# Sensor_Glove_Main-X01.net
KiCad netlist of a schematic drawn in Altium Designer
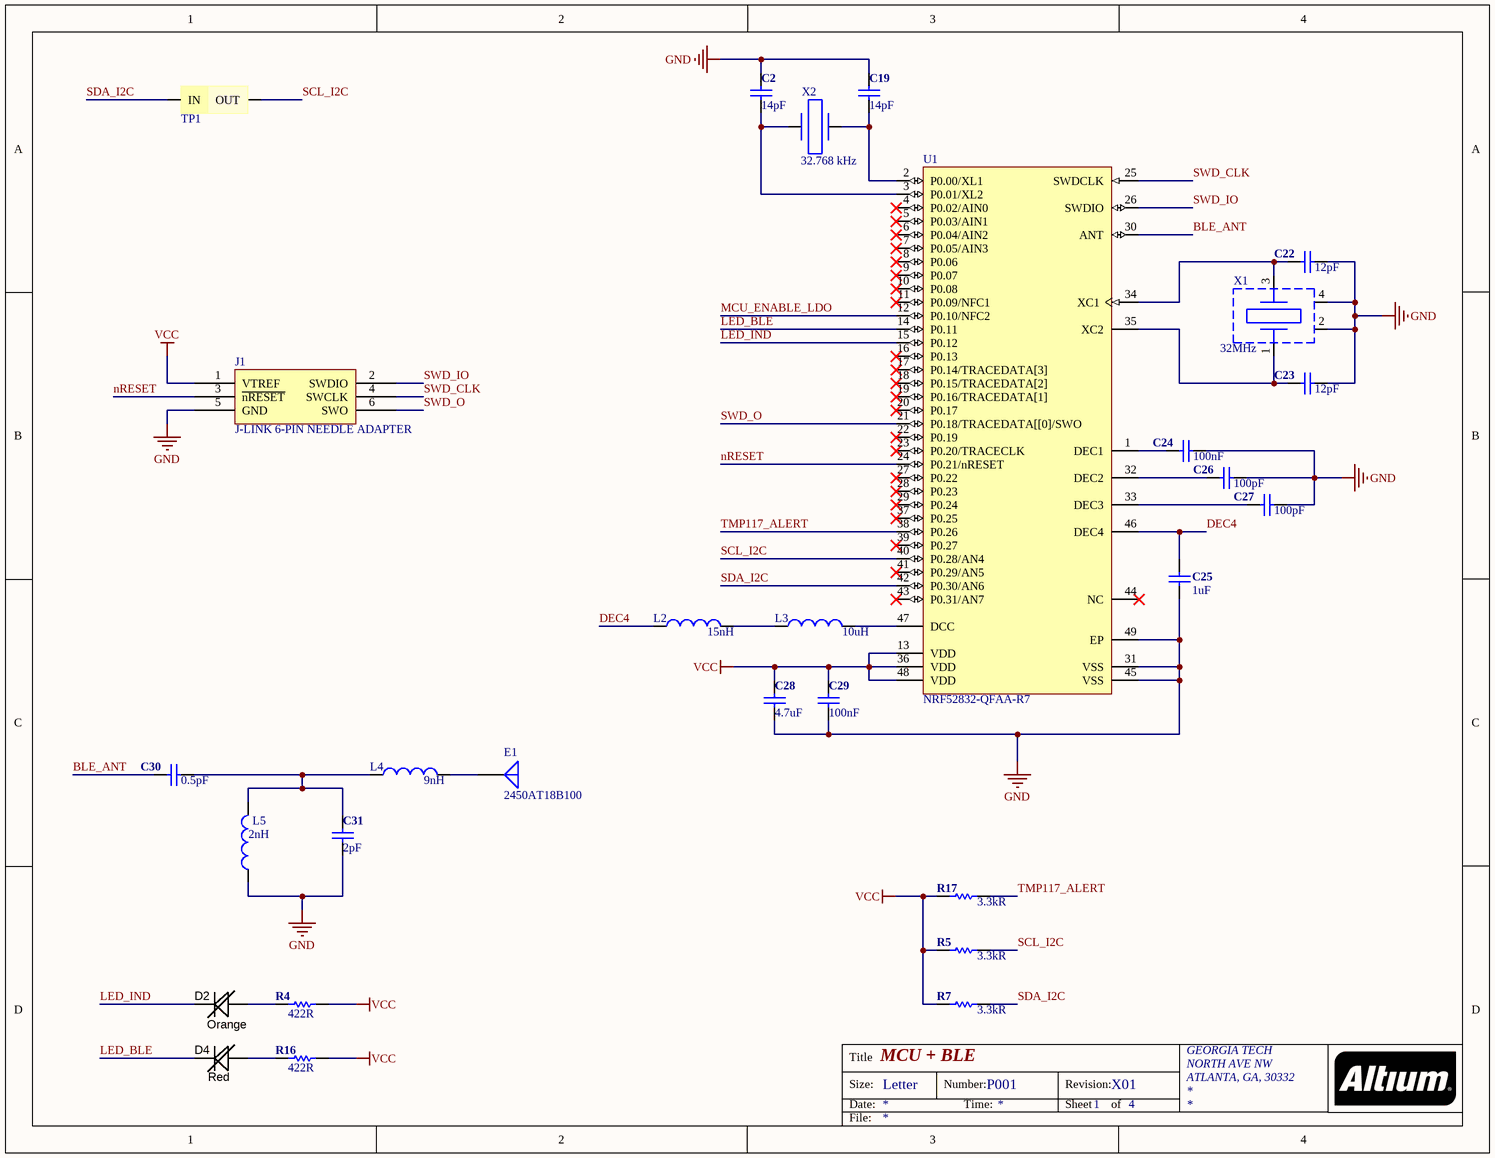
[diagram p0: Sensor_Glove_Main-X01.SchDoc]

(export (version "E")
  (design (tool "Eeschema 10.0.6"))
  (components
    (comp (ref "C2")
      (value "14pF")
      (footprint "C0402")
      (fields
        (field (name "MANUFACTURER") "Kyocera AVX")
        (field (name "MANUFACTURER PART NUMBER") "04025U140FAT2A")
        (field (name "TOLERANCE") "1%")
      )
      (libsource (lib "DB-X01") (part "C-0402(1005)"))
    )
    (comp (ref "C19")
      (value "14pF")
      (footprint "C0402")
      (fields
        (field (name "MANUFACTURER") "Kyocera AVX")
        (field (name "MANUFACTURER PART NUMBER") "04025U140FAT2A")
        (field (name "TOLERANCE") "1%")
      )
      (libsource (lib "DB-X01") (part "C-0402(1005)"))
    )
    (comp (ref "C22")
      (value "12pF")
      (footprint "C0402")
      (fields
        (field (name "MANUFACTURER") "Kyocera AVX")
        (field (name "MANUFACTURER PART NUMBER") "04025U120FAT2A")
        (field (name "TOLERANCE") "1%")
      )
      (libsource (lib "DB-X01") (part "C-0402(1005)"))
    )
    (comp (ref "C23")
      (value "12pF")
      (footprint "C0402")
      (fields
        (field (name "MANUFACTURER") "Kyocera AVX")
        (field (name "MANUFACTURER PART NUMBER") "04025U120FAT2A")
        (field (name "TOLERANCE") "1%")
      )
      (libsource (lib "DB-X01") (part "C-0402(1005)"))
    )
    (comp (ref "C24")
      (value "100nF")
      (footprint "C0402")
      (fields
        (field (name "MANUFACTURER") "Taiyo Yuden")
        (field (name "MANUFACTURER PART NUMBER") "TMK105BJ104KV-F")
        (field (name "TOLERANCE") "10%")
      )
      (libsource (lib "DB-X01") (part "C-0402(1005)"))
    )
    (comp (ref "C25")
      (value "1uF")
      (footprint "C0402")
      (fields
        (field (name "MANUFACTURER") "Yageo")
        (field (name "MANUFACTURER PART NUMBER") "CC0402MRX5R5BB105")
        (field (name "TOLERANCE") "20%")
      )
      (libsource (lib "DB-X01") (part "C-0402(1005)"))
    )
    (comp (ref "C26")
      (value "100pF")
      (footprint "C0402")
      (fields
        (field (name "MANUFACTURER") "Yageo")
        (field (name "MANUFACTURER PART NUMBER") "CC0402FRNPO9BN101")
        (field (name "TOLERANCE") "1%")
      )
      (libsource (lib "DB-X01") (part "C-0402(1005)"))
    )
    (comp (ref "C27")
      (value "100pF")
      (footprint "C0402")
      (fields
        (field (name "MANUFACTURER") "Yageo")
        (field (name "MANUFACTURER PART NUMBER") "CC0402FRNPO9BN101")
        (field (name "TOLERANCE") "1%")
      )
      (libsource (lib "DB-X01") (part "C-0402(1005)"))
    )
    (comp (ref "C28")
      (value "4.7uF")
      (footprint "C0402")
      (description "0402 10 V 4.7 uF ±20% Tolerance X5R Multilayer Ceramic Chip Capacitor")
      (fields
        (field (name "MANUFACTURER") "Murata")
        (field (name "MANUFACTURER PART NUMBER") "GRM155R61A475MEAAD")
      )
      (libsource (lib "DB-X01") (part "C-0402(1005)"))
    )
    (comp (ref "C29")
      (value "100nF")
      (footprint "C0402")
      (fields
        (field (name "MANUFACTURER") "Taiyo Yuden")
        (field (name "MANUFACTURER PART NUMBER") "TMK105BJ104KV-F")
        (field (name "TOLERANCE") "10%")
      )
      (libsource (lib "Sensor_Glove-X01") (part "C-0402(1005)"))
    )
    (comp (ref "C30")
      (value "0.5pF")
      (footprint "C0402")
      (fields
        (field (name "MANUFACTURER") "Murata")
        (field (name "MANUFACTURER PART NUMBER") "GJM1555C1HR50WB01D")
        (field (name "VOLTAGE") "50V")
      )
      (libsource (lib "DB-X01") (part "C-0402(1005)"))
    )
    (comp (ref "C31")
      (value "2pF")
      (footprint "C0402")
      (fields
        (field (name "MANUFACTURER") "Murata")
        (field (name "MANUFACTURER PART NUMBER") "GJM1555C1H2R0BB01D")
      )
      (libsource (lib "DB-X01") (part "C-0402(1005)"))
    )
    (comp (ref "D2")
      (value "Orange")
      (footprint "LED_0402")
      (description "Single Color LED, Super Bright Orange, Water Clear, 0.8mm")
      (fields
        (field (name "MANUFACTURER") "Kingbright")
        (field (name "MANUFACTURER PART NUMBER") "APHHS1005SECK")
      )
      (libsource (lib "DB-X01") (part "LED_0402(1005)"))
    )
    (comp (ref "D4")
      (value "Red")
      (footprint "LED_0402")
      (description "Single Color LED, Hyper Red, Water Clear, 0.8mm")
      (fields
        (field (name "MANUFACTURER") "Kingbright")
        (field (name "MANUFACTURER PART NUMBER") "APHHS1005SURCK")
      )
      (libsource (lib "DB-X01") (part "LED_0402(1005)"))
    )
    (comp (ref "E1")
      (value "2450AT18B100")
      (footprint "2450AT18B100")
      (description "2.4 GHz BLE Antenna")
      (fields
        (field (name "MANUFACTURER") "Johanson")
        (field (name "MANUFACTURER PART NUMBER") "2450AT18B100E")
      )
      (libsource (lib "DB-X01") (part "2450AT18B100"))
    )
    (comp (ref "J1")
      (value "J-LINK 6-PIN NEEDLE ADAPTER")
      (footprint "J-LINK 6 PIN NEEDLE")
      (fields
        (field (name "MANUFACTURER") "Segger")
        (field (name "MANUFACTURER PART NUMBER") "8.06.16 J-LINK 6-PIN NEEDLE ADAPTER")
      )
      (libsource (lib "Sensor_Glove-X01") (part "J-Link 6 pin needle"))
    )
    (comp (ref "L2")
      (value "15nH")
      (footprint "L0402")
      (description "General Purpose Inductor, 0.015uH, 5%, 1 Element, Ferrite-Core, SMD, 0402")
      (fields
        (field (name "MANUFACTURER") "Taiyo Yuden")
        (field (name "MANUFACTURER PART NUMBER") "HK100515NJ-T")
      )
      (libsource (lib "DB-X01") (part "I-0402(1005)"))
    )
    (comp (ref "L3")
      (value "10uH")
      (footprint "L0603")
      (description "General Purpose Inductor, 10uH, 10%, 1 Element, Ferrite-Core, SMD, 0603")
      (fields
        (field (name "MANUFACTURER") "Taiyo Yuden")
        (field (name "MANUFACTURER PART NUMBER") "CBMF1608T100K")
      )
      (libsource (lib "DB-X01") (part "I-0603(1608)"))
    )
    (comp (ref "L4")
      (value "9nH")
      (footprint "L0402")
      (description "General Purpose Inductor, 0.009uH, 2%, 1 Element, SMD")
      (fields
        (field (name "MANUFACTURER") "Murata")
        (field (name "MANUFACTURER PART NUMBER") "LQW15AN9N0G80D")
      )
      (libsource (lib "DB-X01") (part "I-0402(1005)"))
    )
    (comp (ref "L5")
      (value "2nH")
      (footprint "L0402")
      (description "General Purpose Inductor, 0.002uH, 5%, 1 Element, Ceramic-Core, SMD, 0402")
      (fields
        (field (name "MANUFACTURER") "Abracon")
        (field (name "MANUFACTURER PART NUMBER") "AISC-0402-2N0J-T")
      )
      (libsource (lib "DB-X01") (part "I-0402(1005)"))
    )
    (comp (ref "R4")
      (value "422R")
      (footprint "R0402")
      (description "Fixed Resistor, Thin Film, 0.0625W, 422ohm, 50V, 0.1% +/-Tol, 25ppm/Cel, Surface Mount, 0402")
      (fields
        (field (name "MANUFACTURER") "Yageo")
        (field (name "MANUFACTURER PART NUMBER") "RT0402BRD07422RL")
      )
      (libsource (lib "DB-X01") (part "R-0402(1005)"))
    )
    (comp (ref "R5")
      (value "3.3kR")
      (footprint "R0402")
      (fields
        (field (name "MANUFACTURER") "Yageo")
        (field (name "MANUFACTURER PART NUMBER") "AC0402FR-073K3L")
        (field (name "TOLERANCE") "1%")
      )
      (libsource (lib "DB-X01") (part "R-0402(1005)"))
    )
    (comp (ref "R7")
      (value "3.3kR")
      (footprint "R0402")
      (fields
        (field (name "MANUFACTURER") "Yageo")
        (field (name "MANUFACTURER PART NUMBER") "AC0402FR-073K3L")
        (field (name "TOLERANCE") "1%")
      )
      (libsource (lib "DB-X01") (part "R-0402(1005)"))
    )
    (comp (ref "R16")
      (value "422R")
      (footprint "R0402")
      (description "Fixed Resistor, Thin Film, 0.0625W, 422ohm, 50V, 0.1% +/-Tol, 25ppm/Cel, Surface Mount, 0402")
      (fields
        (field (name "MANUFACTURER") "Yageo")
        (field (name "MANUFACTURER PART NUMBER") "RT0402BRD07422RL")
      )
      (libsource (lib "DB-X01") (part "R-0402(1005)"))
    )
    (comp (ref "R17")
      (value "3.3kR")
      (footprint "R0402")
      (fields
        (field (name "MANUFACTURER") "Yageo")
        (field (name "MANUFACTURER PART NUMBER") "AC0402FR-073K3L")
        (field (name "TOLERANCE") "1%")
      )
      (libsource (lib "DB-X01") (part "R-0402(1005)"))
    )
    (comp (ref "TP1")
      (value "JUMPER")
      (footprint "JUMPER")
      (description "SHUNT LP W/HANDLE 2 POS 30AU")
      (fields
        (field (name "MANUFACTURER") "TE Connectivity")
        (field (name "MANUFACTURER PART NUMBER") "8815452")
      )
      (libsource (lib "Sensor_Glove-X01") (part "JUMPER"))
    )
    (comp (ref "U1")
      (value "NRF52832-QFAA-R7")
      (footprint "NRF52832-QFAA-R7")
      (fields (field (name "MANUFACTURER") "Nordic Semiconductor"))
      (libsource (lib "DB-X01") (part "NRSC-NRF52832-QF-48"))
    )
    (comp (ref "X1")
      (value "32MHz")
      (footprint "CRYSTAL_1MM6_X_1MM2")
      (description "Parallel - Fundamental Quartz Crystal, 32MHz Nom")
      (fields (field (name "MANUFACTURER") "Diodes") (field (name "MANUFACTURER PART NUMBER") "US3200005Z"))
      (libsource (lib "DB-X01") (part "CRYSTAL_32MHz"))
    )
    (comp (ref "X2")
      (value "32.768 kHz")
      (footprint "CRYSTAL_1MM2_X_1MM0")
      (description "Parallel - Fundamental Quartz Crystal, 0.032768MHz Nom")
      (fields
        (field (name "MANUFACTURER") "ECS International")
        (field (name "MANUFACTURER PART NUMBER") "ECS-.327-9-1210-TR")
      )
      (libsource (lib "DB-X01") (part "CRYSTAL_32K768"))
    )
  )
  (nets
    (net (code "1") (name "/BLE_ANT") (class "Default")
      (node (ref "C30") (pin "1") (pinfunction "1_1") (pintype "passive"))
      (node (ref "U1") (pin "30") (pinfunction "ANT_30") (pintype "bidirectional"))
    )
    (net (code "2") (name "/DEC4") (class "Default")
      (node (ref "C25") (pin "2") (pinfunction "2_2") (pintype "passive"))
      (node (ref "L2") (pin "1") (pinfunction "1_1") (pintype "passive"))
      (node (ref "U1") (pin "46") (pinfunction "DEC4_46") (pintype "passive"))
    )
    (net (code "3") (name "/LED_BLE") (class "Default")
      (node (ref "D4") (pin "K") (pinfunction "K_K") (pintype "passive"))
      (node (ref "U1") (pin "14") (pinfunction "P0.11_14") (pintype "bidirectional"))
    )
    (net (code "4") (name "/LED_IND") (class "Default")
      (node (ref "D2") (pin "K") (pinfunction "K_K") (pintype "passive"))
      (node (ref "U1") (pin "15") (pinfunction "P0.12_15") (pintype "bidirectional"))
    )
    (net (code "5") (name "/MCU_ENABLE_LDO") (class "Default")
      (node (ref "U1") (pin "12") (pinfunction "P0.10/NFC2_12") (pintype "bidirectional"))
    )
    (net (code "6") (name "/SCL_I2C") (class "Default")
      (node (ref "R5") (pin "2") (pinfunction "2_2") (pintype "passive"))
      (node (ref "TP1") (pin "2") (pinfunction "OUT_2") (pintype "passive"))
      (node (ref "U1") (pin "40") (pinfunction "P0.28/AN4_40") (pintype "bidirectional"))
    )
    (net (code "7") (name "/SDA_I2C") (class "Default")
      (node (ref "R7") (pin "2") (pinfunction "2_2") (pintype "passive"))
      (node (ref "TP1") (pin "1") (pinfunction "IN_1") (pintype "passive"))
      (node (ref "U1") (pin "42") (pinfunction "P0.30/AN6_42") (pintype "bidirectional"))
    )
    (net (code "8") (name "/SWD_CLK") (class "Default")
      (node (ref "J1") (pin "4") (pinfunction "SWCLK_4") (pintype "passive"))
      (node (ref "U1") (pin "25") (pinfunction "SWDCLK_25") (pintype "input"))
    )
    (net (code "9") (name "/SWD_IO") (class "Default")
      (node (ref "J1") (pin "2") (pinfunction "SWDIO_2") (pintype "passive"))
      (node (ref "U1") (pin "26") (pinfunction "SWDIO_26") (pintype "bidirectional"))
    )
    (net (code "10") (name "/SWD_O") (class "Default")
      (node (ref "J1") (pin "6") (pinfunction "SWO_6") (pintype "passive"))
      (node (ref "U1") (pin "21") (pinfunction "P0.18/TRACEDATA[[0]/SWO_21") (pintype "bidirectional"))
    )
    (net (code "11") (name "/TMP117_ALERT") (class "Default")
      (node (ref "R17") (pin "2") (pinfunction "2_2") (pintype "passive"))
      (node (ref "U1") (pin "38") (pinfunction "P0.26_38") (pintype "bidirectional"))
    )
    (net (code "12") (name "/nRESET") (class "Default")
      (node (ref "J1") (pin "3") (pinfunction "~{nRESET}_3") (pintype "passive"))
      (node (ref "U1") (pin "24") (pinfunction "P0.21/nRESET_24") (pintype "bidirectional"))
    )
    (net (code "13") (name "GND") (class "Default")
      (node (ref "C19") (pin "1") (pinfunction "1_1") (pintype "passive"))
      (node (ref "C2") (pin "1") (pinfunction "1_1") (pintype "passive"))
      (node (ref "C22") (pin "2") (pinfunction "2_2") (pintype "passive"))
      (node (ref "C23") (pin "2") (pinfunction "2_2") (pintype "passive"))
      (node (ref "C24") (pin "2") (pinfunction "2_2") (pintype "passive"))
      (node (ref "C25") (pin "1") (pinfunction "1_1") (pintype "passive"))
      (node (ref "C26") (pin "2") (pinfunction "2_2") (pintype "passive"))
      (node (ref "C27") (pin "2") (pinfunction "2_2") (pintype "passive"))
      (node (ref "C28") (pin "2") (pinfunction "2_2") (pintype "passive"))
      (node (ref "C29") (pin "1") (pinfunction "1_1") (pintype "passive"))
      (node (ref "C31") (pin "2") (pinfunction "2_2") (pintype "passive"))
      (node (ref "J1") (pin "5") (pinfunction "GND_5") (pintype "passive"))
      (node (ref "L5") (pin "1") (pinfunction "1_1") (pintype "passive"))
      (node (ref "U1") (pin "31") (pinfunction "VSS_31") (pintype "power_in"))
      (node (ref "U1") (pin "45") (pinfunction "VSS_45") (pintype "power_in"))
      (node (ref "U1") (pin "49") (pinfunction "EP_49") (pintype "power_in"))
      (node (ref "X1") (pin "2") (pinfunction "GND_2") (pintype "passive"))
      (node (ref "X1") (pin "4") (pinfunction "GND_4") (pintype "passive"))
    )
    (net (code "14") (name "Net-(C30-Pad2)") (class "Default")
      (node (ref "C30") (pin "2") (pinfunction "2_2") (pintype "passive"))
      (node (ref "C31") (pin "1") (pinfunction "1_1") (pintype "passive"))
      (node (ref "L4") (pin "1") (pinfunction "1_1") (pintype "passive"))
      (node (ref "L5") (pin "2") (pinfunction "2_2") (pintype "passive"))
    )
    (net (code "15") (name "Net-(D2-PadA)") (class "Default")
      (node (ref "D2") (pin "A") (pinfunction "A_A") (pintype "passive"))
      (node (ref "R4") (pin "2") (pinfunction "2_2") (pintype "passive"))
    )
    (net (code "16") (name "Net-(D4-PadA)") (class "Default")
      (node (ref "D4") (pin "A") (pinfunction "A_A") (pintype "passive"))
      (node (ref "R16") (pin "2") (pinfunction "2_2") (pintype "passive"))
    )
    (net (code "17") (name "Net-(E1-A)") (class "Default")
      (node (ref "E1") (pin "1") (pinfunction "A_1") (pintype "passive"))
      (node (ref "L4") (pin "2") (pinfunction "2_2") (pintype "passive"))
    )
    (net (code "18") (name "Net-(L2-Pad2)") (class "Default")
      (node (ref "L2") (pin "2") (pinfunction "2_2") (pintype "passive"))
      (node (ref "L3") (pin "1") (pinfunction "1_1") (pintype "passive"))
    )
    (net (code "19") (name "Net-(U1-DCC)") (class "Default")
      (node (ref "L3") (pin "2") (pinfunction "2_2") (pintype "passive"))
      (node (ref "U1") (pin "47") (pinfunction "DCC_47") (pintype "power_in"))
    )
    (net (code "20") (name "Net-(U1-DEC1)") (class "Default")
      (node (ref "C24") (pin "1") (pinfunction "1_1") (pintype "passive"))
      (node (ref "U1") (pin "1") (pinfunction "DEC1_1") (pintype "passive"))
    )
    (net (code "21") (name "Net-(U1-DEC2)") (class "Default")
      (node (ref "C26") (pin "1") (pinfunction "1_1") (pintype "passive"))
      (node (ref "U1") (pin "32") (pinfunction "DEC2_32") (pintype "passive"))
    )
    (net (code "22") (name "Net-(U1-DEC3)") (class "Default")
      (node (ref "C27") (pin "1") (pinfunction "1_1") (pintype "passive"))
      (node (ref "U1") (pin "33") (pinfunction "DEC3_33") (pintype "passive"))
    )
    (net (code "23") (name "Net-(U1-P0.00{slash}XL1)") (class "Default")
      (node (ref "C19") (pin "2") (pinfunction "2_2") (pintype "passive"))
      (node (ref "U1") (pin "2") (pinfunction "P0.00/XL1_2") (pintype "bidirectional"))
      (node (ref "X2") (pin "2") (pinfunction "2_2") (pintype "passive"))
    )
    (net (code "24") (name "Net-(U1-P0.01{slash}XL2)") (class "Default")
      (node (ref "C2") (pin "2") (pinfunction "2_2") (pintype "passive"))
      (node (ref "U1") (pin "3") (pinfunction "P0.01/XL2_3") (pintype "bidirectional"))
      (node (ref "X2") (pin "1") (pinfunction "1_1") (pintype "passive"))
    )
    (net (code "25") (name "Net-(U1-XC1)") (class "Default")
      (node (ref "C22") (pin "1") (pinfunction "1_1") (pintype "passive"))
      (node (ref "U1") (pin "34") (pinfunction "XC1_34") (pintype "input"))
      (node (ref "X1") (pin "3") (pinfunction "3_3") (pintype "passive"))
    )
    (net (code "26") (name "Net-(U1-XC2)") (class "Default")
      (node (ref "C23") (pin "1") (pinfunction "1_1") (pintype "passive"))
      (node (ref "U1") (pin "35") (pinfunction "XC2_35") (pintype "passive"))
      (node (ref "X1") (pin "1") (pinfunction "1_1") (pintype "passive"))
    )
    (net (code "27") (name "VCC") (class "Default")
      (node (ref "C28") (pin "1") (pinfunction "1_1") (pintype "passive"))
      (node (ref "C29") (pin "2") (pinfunction "2_2") (pintype "passive"))
      (node (ref "J1") (pin "1") (pinfunction "VTREF_1") (pintype "passive"))
      (node (ref "R16") (pin "1") (pinfunction "1_1") (pintype "passive"))
      (node (ref "R17") (pin "1") (pinfunction "1_1") (pintype "passive"))
      (node (ref "R4") (pin "1") (pinfunction "1_1") (pintype "passive"))
      (node (ref "R5") (pin "1") (pinfunction "1_1") (pintype "passive"))
      (node (ref "R7") (pin "1") (pinfunction "1_1") (pintype "passive"))
      (node (ref "U1") (pin "13") (pinfunction "VDD_13") (pintype "power_in"))
      (node (ref "U1") (pin "36") (pinfunction "VDD_36") (pintype "power_in"))
      (node (ref "U1") (pin "48") (pinfunction "VDD_48") (pintype "power_in"))
    )
    (net (code "28") (name "unconnected-(U1-NC-Pad44)") (class "Default")
      (node (ref "U1") (pin "44") (pinfunction "NC_44") (pintype "passive+no_connect"))
    )
    (net (code "29") (name "unconnected-(U1-P0.02{slash}AIN0-Pad4)") (class "Default")
      (node (ref "U1") (pin "4") (pinfunction "P0.02/AIN0_4") (pintype "bidirectional+no_connect"))
    )
    (net (code "30") (name "unconnected-(U1-P0.03{slash}AIN1-Pad5)") (class "Default")
      (node (ref "U1") (pin "5") (pinfunction "P0.03/AIN1_5") (pintype "bidirectional+no_connect"))
    )
    (net (code "31") (name "unconnected-(U1-P0.04{slash}AIN2-Pad6)") (class "Default")
      (node (ref "U1") (pin "6") (pinfunction "P0.04/AIN2_6") (pintype "bidirectional+no_connect"))
    )
    (net (code "32") (name "unconnected-(U1-P0.05{slash}AIN3-Pad7)") (class "Default")
      (node (ref "U1") (pin "7") (pinfunction "P0.05/AIN3_7") (pintype "bidirectional+no_connect"))
    )
    (net (code "33") (name "unconnected-(U1-P0.06-Pad8)") (class "Default")
      (node (ref "U1") (pin "8") (pinfunction "P0.06_8") (pintype "bidirectional+no_connect"))
    )
    (net (code "34") (name "unconnected-(U1-P0.07-Pad9)") (class "Default")
      (node (ref "U1") (pin "9") (pinfunction "P0.07_9") (pintype "bidirectional+no_connect"))
    )
    (net (code "35") (name "unconnected-(U1-P0.08-Pad10)") (class "Default")
      (node (ref "U1") (pin "10") (pinfunction "P0.08_10") (pintype "bidirectional+no_connect"))
    )
    (net (code "36") (name "unconnected-(U1-P0.09{slash}NFC1-Pad11)") (class "Default")
      (node (ref "U1") (pin "11") (pinfunction "P0.09/NFC1_11") (pintype "bidirectional+no_connect"))
    )
    (net (code "37") (name "unconnected-(U1-P0.13-Pad16)") (class "Default")
      (node (ref "U1") (pin "16") (pinfunction "P0.13_16") (pintype "bidirectional+no_connect"))
    )
    (net (code "38") (name "unconnected-(U1-P0.14{slash}TRACEDATA[3]-Pad17)") (class "Default")
      (node (ref "U1") (pin "17") (pinfunction "P0.14/TRACEDATA[3]_17") (pintype "bidirectional+no_connect"))
    )
    (net (code "39") (name "unconnected-(U1-P0.15{slash}TRACEDATA[2]-Pad18)") (class "Default")
      (node (ref "U1") (pin "18") (pinfunction "P0.15/TRACEDATA[2]_18") (pintype "bidirectional+no_connect"))
    )
    (net (code "40") (name "unconnected-(U1-P0.16{slash}TRACEDATA[1]-Pad19)") (class "Default")
      (node (ref "U1") (pin "19") (pinfunction "P0.16/TRACEDATA[1]_19") (pintype "bidirectional+no_connect"))
    )
    (net (code "41") (name "unconnected-(U1-P0.17-Pad20)") (class "Default")
      (node (ref "U1") (pin "20") (pinfunction "P0.17_20") (pintype "bidirectional+no_connect"))
    )
    (net (code "42") (name "unconnected-(U1-P0.19-Pad22)") (class "Default")
      (node (ref "U1") (pin "22") (pinfunction "P0.19_22") (pintype "bidirectional+no_connect"))
    )
    (net (code "43") (name "unconnected-(U1-P0.20{slash}TRACECLK-Pad23)") (class "Default")
      (node (ref "U1") (pin "23") (pinfunction "P0.20/TRACECLK_23") (pintype "bidirectional+no_connect"))
    )
    (net (code "44") (name "unconnected-(U1-P0.22-Pad27)") (class "Default")
      (node (ref "U1") (pin "27") (pinfunction "P0.22_27") (pintype "bidirectional+no_connect"))
    )
    (net (code "45") (name "unconnected-(U1-P0.23-Pad28)") (class "Default")
      (node (ref "U1") (pin "28") (pinfunction "P0.23_28") (pintype "bidirectional+no_connect"))
    )
    (net (code "46") (name "unconnected-(U1-P0.24-Pad29)") (class "Default")
      (node (ref "U1") (pin "29") (pinfunction "P0.24_29") (pintype "bidirectional+no_connect"))
    )
    (net (code "47") (name "unconnected-(U1-P0.25-Pad37)") (class "Default")
      (node (ref "U1") (pin "37") (pinfunction "P0.25_37") (pintype "bidirectional+no_connect"))
    )
    (net (code "48") (name "unconnected-(U1-P0.27-Pad39)") (class "Default")
      (node (ref "U1") (pin "39") (pinfunction "P0.27_39") (pintype "bidirectional+no_connect"))
    )
    (net (code "49") (name "unconnected-(U1-P0.29{slash}AN5-Pad41)") (class "Default")
      (node (ref "U1") (pin "41") (pinfunction "P0.29/AN5_41") (pintype "bidirectional+no_connect"))
    )
    (net (code "50") (name "unconnected-(U1-P0.31{slash}AN7-Pad43)") (class "Default")
      (node (ref "U1") (pin "43") (pinfunction "P0.31/AN7_43") (pintype "bidirectional+no_connect"))
    )
  )
)
